# DRAM_DDR4.net
KiCad netlist of a schematic drawn in Altium Designer
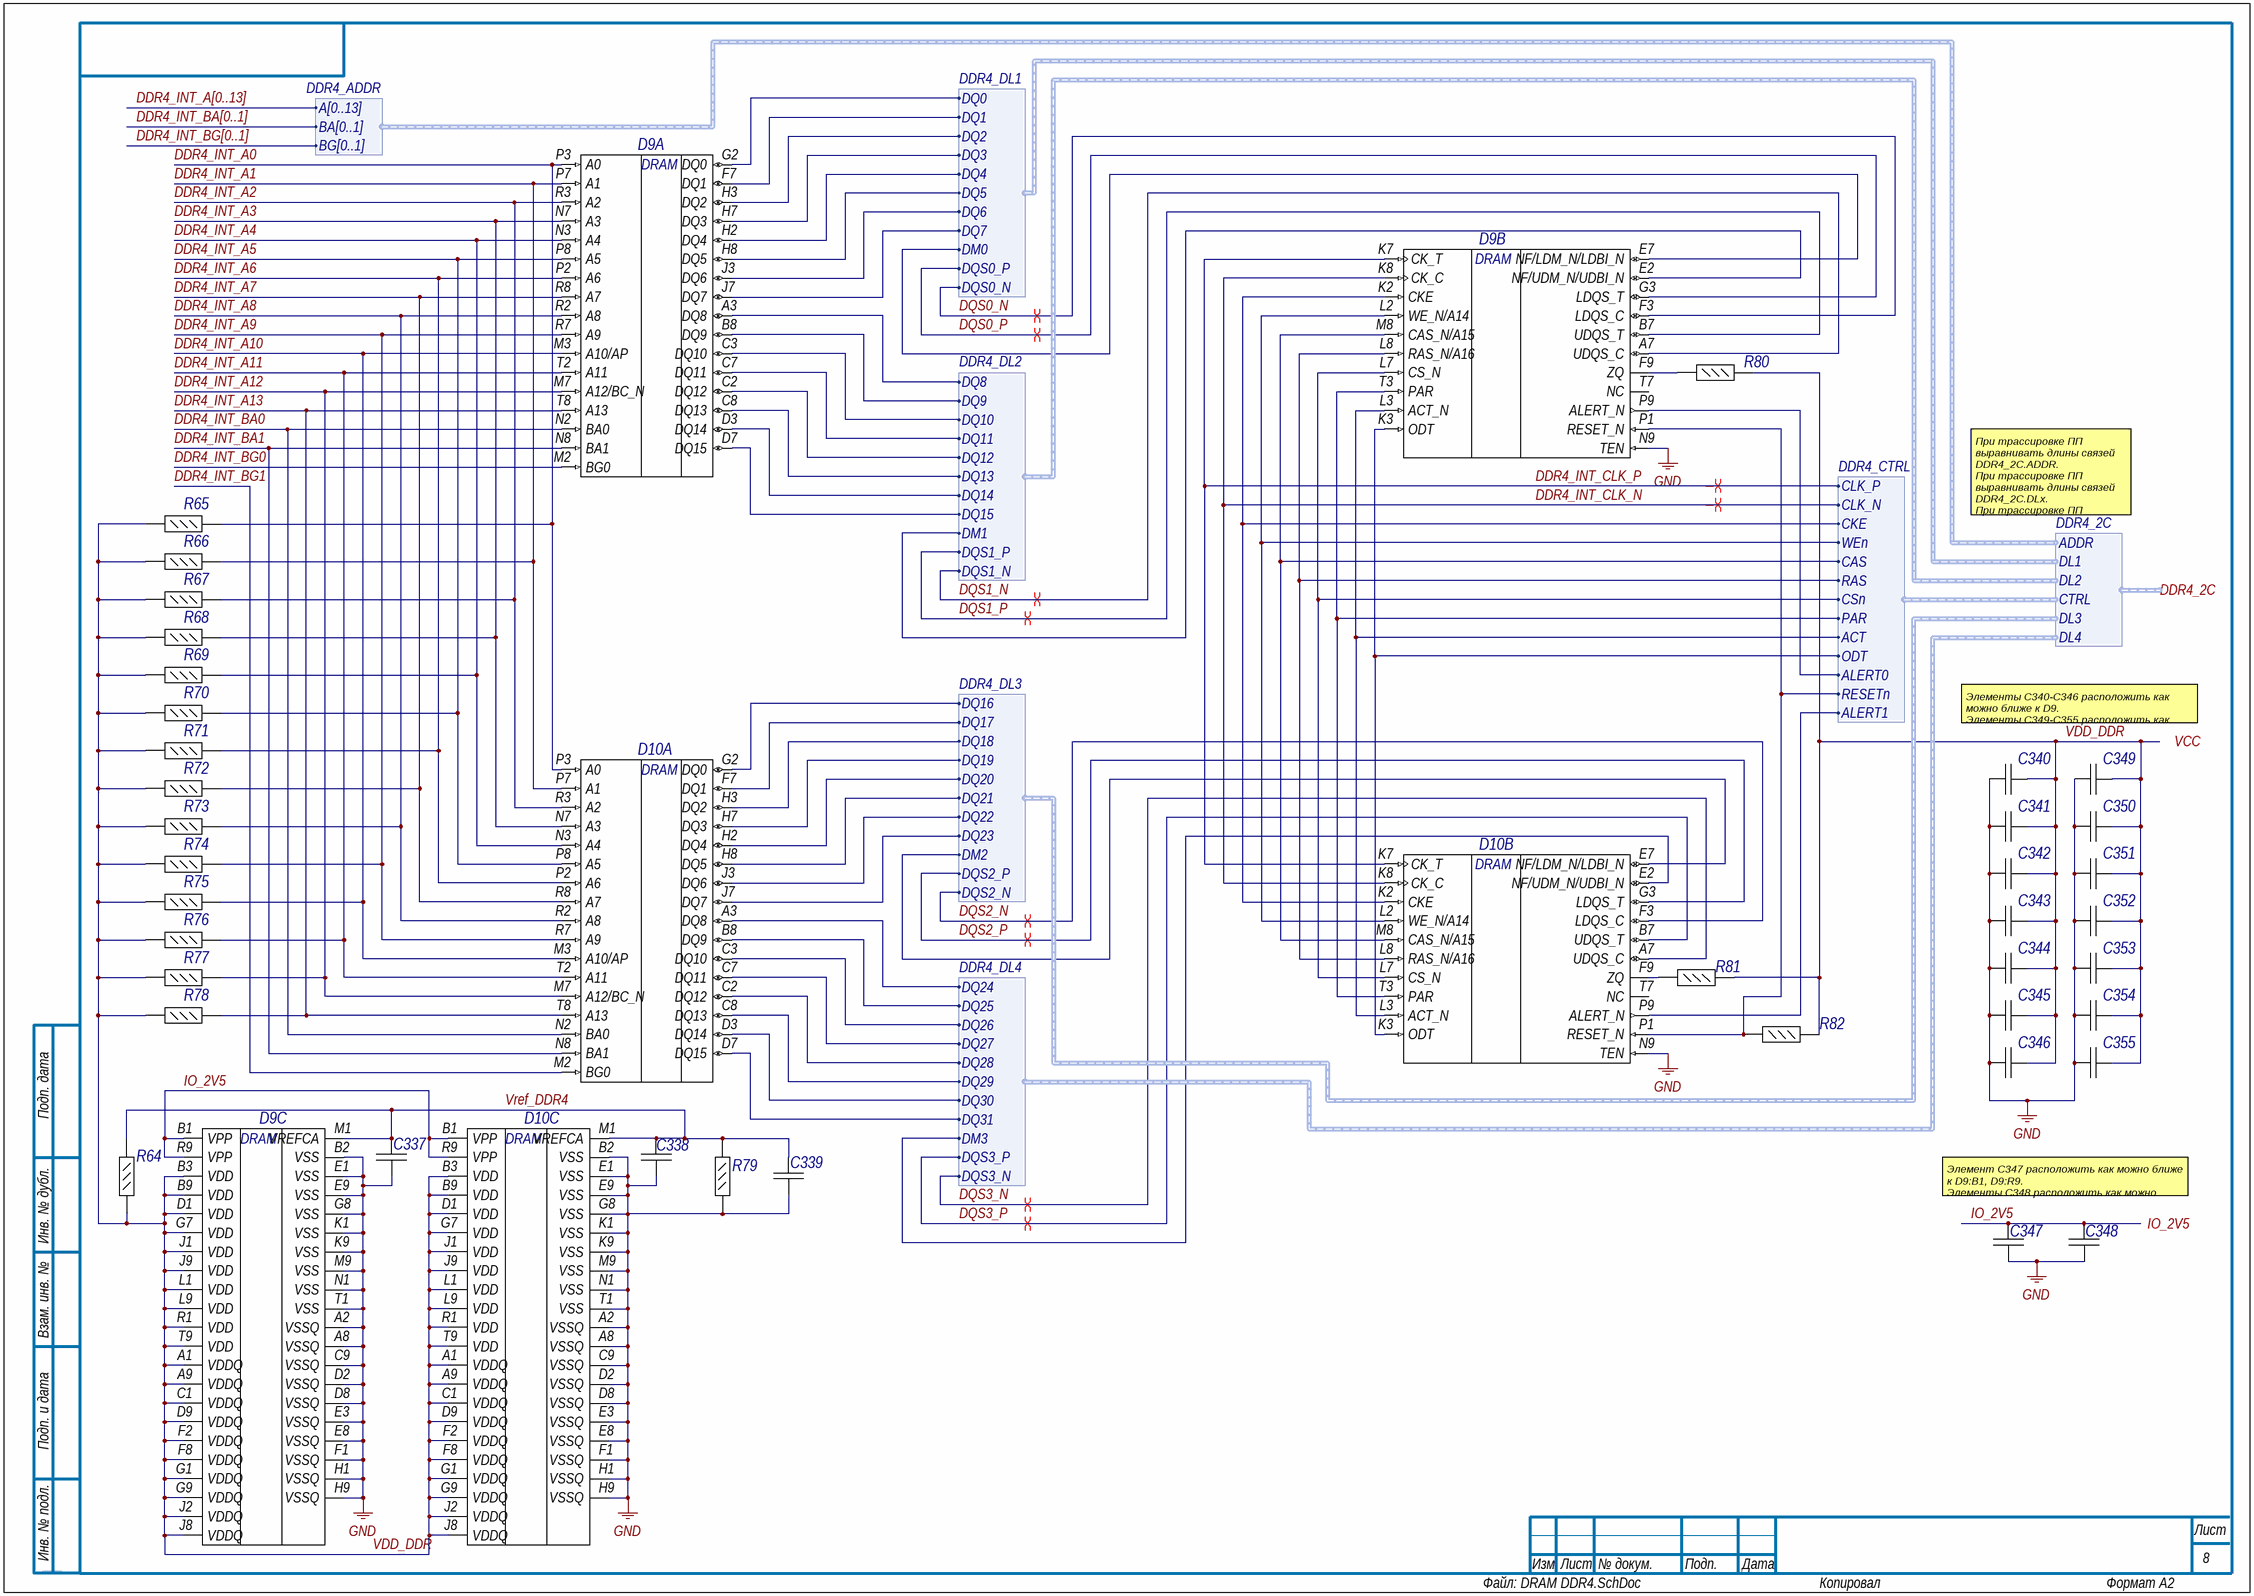
[diagram p0: DRAM DDR4.SchDoc]

(export (version "E")
  (design (tool "Eeschema 10.0.6"))
  (components
    (comp (ref "C337")
      (value "GRM033R60J104KE19D")
      (footprint "CAPC0603X33X15LL03T05")
      (description "Chip Capacitor, 100 nF, +/- 10%, 6.3 V, -55 to 85 degC, 0201 (0603 Metric), RoHS, Tape and Reel")
      (fields (field (name "TOLERANCE") "10%") (field (name "MANUFACTURER") "Basic Passives"))
      (libsource (lib "MiniPC DB") (part "CAP_NP"))
    )
    (comp (ref "C338")
      (value "GRM033R60J104KE19D")
      (footprint "CAPC0603X33X15LL03T05")
      (description "Chip Capacitor, 100 nF, +/- 10%, 6.3 V, -55 to 85 degC, 0201 (0603 Metric), RoHS, Tape and Reel")
      (fields (field (name "TOLERANCE") "10%") (field (name "MANUFACTURER") "Basic Passives"))
      (libsource (lib "MiniPC DB") (part "CAP_NP"))
    )
    (comp (ref "C339")
      (value "GRM033R60J104KE19D")
      (footprint "CAPC0603X33X15LL03T05")
      (description "Chip Capacitor, 100 nF, +/- 10%, 6.3 V, -55 to 85 degC, 0201 (0603 Metric), RoHS, Tape and Reel")
      (fields (field (name "TOLERANCE") "10%") (field (name "MANUFACTURER") "Basic Passives"))
      (libsource (lib "MiniPC DB") (part "CAP_NP"))
    )
    (comp (ref "C340")
      (value "GRM033R60J104KE19D")
      (footprint "CAPC0603X33X15LL03T05")
      (description "Chip Capacitor, 100 nF, +/- 10%, 6.3 V, -55 to 85 degC, 0201 (0603 Metric), RoHS, Tape and Reel")
      (fields (field (name "TOLERANCE") "10%") (field (name "MANUFACTURER") "Basic Passives"))
      (libsource (lib "MiniPC DB") (part "CAP_NP"))
    )
    (comp (ref "C341")
      (value "GRM033R60J104KE19D")
      (footprint "CAPC0603X33X15LL03T05")
      (description "Chip Capacitor, 100 nF, +/- 10%, 6.3 V, -55 to 85 degC, 0201 (0603 Metric), RoHS, Tape and Reel")
      (fields (field (name "TOLERANCE") "10%") (field (name "MANUFACTURER") "Basic Passives"))
      (libsource (lib "MiniPC DB") (part "CAP_NP"))
    )
    (comp (ref "C342")
      (value "GRM033R60J104KE19D")
      (footprint "CAPC0603X33X15LL03T05")
      (description "Chip Capacitor, 100 nF, +/- 10%, 6.3 V, -55 to 85 degC, 0201 (0603 Metric), RoHS, Tape and Reel")
      (fields (field (name "TOLERANCE") "10%") (field (name "MANUFACTURER") "Basic Passives"))
      (libsource (lib "MiniPC DB") (part "CAP_NP"))
    )
    (comp (ref "C343")
      (value "GRM033R60J104KE19D")
      (footprint "CAPC0603X33X15LL03T05")
      (description "Chip Capacitor, 100 nF, +/- 10%, 6.3 V, -55 to 85 degC, 0201 (0603 Metric), RoHS, Tape and Reel")
      (fields (field (name "TOLERANCE") "10%") (field (name "MANUFACTURER") "Basic Passives"))
      (libsource (lib "MiniPC DB") (part "CAP_NP"))
    )
    (comp (ref "C344")
      (value "GRM033R60J104KE19D")
      (footprint "CAPC0603X33X15LL03T05")
      (description "Chip Capacitor, 100 nF, +/- 10%, 6.3 V, -55 to 85 degC, 0201 (0603 Metric), RoHS, Tape and Reel")
      (fields (field (name "TOLERANCE") "10%") (field (name "MANUFACTURER") "Basic Passives"))
      (libsource (lib "MiniPC DB") (part "CAP_NP"))
    )
    (comp (ref "C345")
      (value "GRM033R60J104KE19D")
      (footprint "CAPC0603X33X15LL03T05")
      (description "Chip Capacitor, 100 nF, +/- 10%, 6.3 V, -55 to 85 degC, 0201 (0603 Metric), RoHS, Tape and Reel")
      (fields (field (name "TOLERANCE") "10%") (field (name "MANUFACTURER") "Basic Passives"))
      (libsource (lib "MiniPC DB") (part "CAP_NP"))
    )
    (comp (ref "C346")
      (value "GRM033R60J104KE19D")
      (footprint "CAPC0603X33X15LL03T05")
      (description "Chip Capacitor, 100 nF, +/- 10%, 6.3 V, -55 to 85 degC, 0201 (0603 Metric), RoHS, Tape and Reel")
      (fields (field (name "TOLERANCE") "10%") (field (name "MANUFACTURER") "Basic Passives"))
      (libsource (lib "MiniPC DB") (part "CAP_NP"))
    )
    (comp (ref "C347")
      (value "GRM033R60J104KE19D")
      (footprint "CAPC0603X33X15LL03T05")
      (description "Chip Capacitor, 100 nF, +/- 10%, 6.3 V, -55 to 85 degC, 0201 (0603 Metric), RoHS, Tape and Reel")
      (fields (field (name "TOLERANCE") "10%") (field (name "MANUFACTURER") "Basic Passives"))
      (libsource (lib "MiniPC DB") (part "CAP_NP"))
    )
    (comp (ref "C348")
      (value "GRM033R60J104KE19D")
      (footprint "CAPC0603X33X15LL03T05")
      (description "Chip Capacitor, 100 nF, +/- 10%, 6.3 V, -55 to 85 degC, 0201 (0603 Metric), RoHS, Tape and Reel")
      (fields (field (name "TOLERANCE") "10%") (field (name "MANUFACTURER") "Basic Passives"))
      (libsource (lib "MiniPC DB") (part "CAP_NP"))
    )
    (comp (ref "C349")
      (value "GRM033R60J104KE19D")
      (footprint "CAPC0603X33X15LL03T05")
      (description "Chip Capacitor, 100 nF, +/- 10%, 6.3 V, -55 to 85 degC, 0201 (0603 Metric), RoHS, Tape and Reel")
      (fields (field (name "TOLERANCE") "10%") (field (name "MANUFACTURER") "Basic Passives"))
      (libsource (lib "MiniPC DB") (part "CAP_NP"))
    )
    (comp (ref "C350")
      (value "GRM033R60J104KE19D")
      (footprint "CAPC0603X33X15LL03T05")
      (description "Chip Capacitor, 100 nF, +/- 10%, 6.3 V, -55 to 85 degC, 0201 (0603 Metric), RoHS, Tape and Reel")
      (fields (field (name "TOLERANCE") "10%") (field (name "MANUFACTURER") "Basic Passives"))
      (libsource (lib "MiniPC DB") (part "CAP_NP"))
    )
    (comp (ref "C351")
      (value "GRM033R60J104KE19D")
      (footprint "CAPC0603X33X15LL03T05")
      (description "Chip Capacitor, 100 nF, +/- 10%, 6.3 V, -55 to 85 degC, 0201 (0603 Metric), RoHS, Tape and Reel")
      (fields (field (name "TOLERANCE") "10%") (field (name "MANUFACTURER") "Basic Passives"))
      (libsource (lib "MiniPC DB") (part "CAP_NP"))
    )
    (comp (ref "C352")
      (value "GRM033R60J104KE19D")
      (footprint "CAPC0603X33X15LL03T05")
      (description "Chip Capacitor, 100 nF, +/- 10%, 6.3 V, -55 to 85 degC, 0201 (0603 Metric), RoHS, Tape and Reel")
      (fields (field (name "TOLERANCE") "10%") (field (name "MANUFACTURER") "Basic Passives"))
      (libsource (lib "MiniPC DB") (part "CAP_NP"))
    )
    (comp (ref "C353")
      (value "GRM033R60J104KE19D")
      (footprint "CAPC0603X33X15LL03T05")
      (description "Chip Capacitor, 100 nF, +/- 10%, 6.3 V, -55 to 85 degC, 0201 (0603 Metric), RoHS, Tape and Reel")
      (fields (field (name "TOLERANCE") "10%") (field (name "MANUFACTURER") "Basic Passives"))
      (libsource (lib "MiniPC DB") (part "CAP_NP"))
    )
    (comp (ref "C354")
      (value "GRM033R60J104KE19D")
      (footprint "CAPC0603X33X15LL03T05")
      (description "Chip Capacitor, 100 nF, +/- 10%, 6.3 V, -55 to 85 degC, 0201 (0603 Metric), RoHS, Tape and Reel")
      (fields (field (name "TOLERANCE") "10%") (field (name "MANUFACTURER") "Basic Passives"))
      (libsource (lib "MiniPC DB") (part "CAP_NP"))
    )
    (comp (ref "C355")
      (value "GRM033R60J104KE19D")
      (footprint "CAPC0603X33X15LL03T05")
      (description "Chip Capacitor, 100 nF, +/- 10%, 6.3 V, -55 to 85 degC, 0201 (0603 Metric), RoHS, Tape and Reel")
      (fields (field (name "TOLERANCE") "10%") (field (name "MANUFACTURER") "Basic Passives"))
      (libsource (lib "MiniPC DB") (part "CAP_NP"))
    )
    (comp (ref "D9")
      (value "MT40A512M16LY-107E")
      (footprint "MICT-LY-96_A")
      (description "8 Gb DDR4 SDRAM, 512 Meg x 16, 1.2 V, 0 to 95 degC, 96-Ball FBGA (LY), RoHS")
      (libsource (lib "MiniPC DB") (part "MT40A512M16"))
    )
    (comp (ref "D10")
      (value "MT40A512M16LY-107E")
      (footprint "MICT-LY-96_A")
      (description "8 Gb DDR4 SDRAM, 512 Meg x 16, 1.2 V, 0 to 95 degC, 96-Ball FBGA (LY), RoHS")
      (libsource (lib "MiniPC DB") (part "MT40A512M16"))
    )
    (comp (ref "R64")
      (value "ERJ-2RKF2400X")
      (footprint "RESC1005X40X25LL05T05")
      (description "Chip Resistor, 240 Ohm, +/- 1%, 100 mW, -55 to 155 degC, 0402 (1005 Metric), RoHS, Tape and Reel")
      (fields (field (name "TOLERANCE") "1%"))
      (libsource (lib "") (part "RES-0.05_1"))
    )
    (comp (ref "R65")
      (value "RC0402JR-0739RL")
      (footprint "RESC1005X40X25LL05T05")
      (description "Chip Resistor, 39 Ohm, +/- 5%, 0.063 W, -55 to 155 degC, 0402 (1005 Metric), RoHS, Tape and Reel")
      (fields (field (name "TOLERANCE") "5%"))
      (libsource (lib "MiniPC DB") (part "RES-0.05"))
    )
    (comp (ref "R66")
      (value "RC0402JR-0739RL")
      (footprint "RESC1005X40X25LL05T05")
      (description "Chip Resistor, 39 Ohm, +/- 5%, 0.063 W, -55 to 155 degC, 0402 (1005 Metric), RoHS, Tape and Reel")
      (fields (field (name "TOLERANCE") "5%"))
      (libsource (lib "MiniPC DB") (part "RES-0.05"))
    )
    (comp (ref "R67")
      (value "RC0402JR-0739RL")
      (footprint "RESC1005X40X25LL05T05")
      (description "Chip Resistor, 39 Ohm, +/- 5%, 0.063 W, -55 to 155 degC, 0402 (1005 Metric), RoHS, Tape and Reel")
      (fields (field (name "TOLERANCE") "5%"))
      (libsource (lib "MiniPC DB") (part "RES-0.05"))
    )
    (comp (ref "R68")
      (value "RC0402JR-0739RL")
      (footprint "RESC1005X40X25LL05T05")
      (description "Chip Resistor, 39 Ohm, +/- 5%, 0.063 W, -55 to 155 degC, 0402 (1005 Metric), RoHS, Tape and Reel")
      (fields (field (name "TOLERANCE") "5%"))
      (libsource (lib "MiniPC DB") (part "RES-0.05"))
    )
    (comp (ref "R69")
      (value "RC0402JR-0739RL")
      (footprint "RESC1005X40X25LL05T05")
      (description "Chip Resistor, 39 Ohm, +/- 5%, 0.063 W, -55 to 155 degC, 0402 (1005 Metric), RoHS, Tape and Reel")
      (fields (field (name "TOLERANCE") "5%"))
      (libsource (lib "MiniPC DB") (part "RES-0.05"))
    )
    (comp (ref "R70")
      (value "RC0402JR-0739RL")
      (footprint "RESC1005X40X25LL05T05")
      (description "Chip Resistor, 39 Ohm, +/- 5%, 0.063 W, -55 to 155 degC, 0402 (1005 Metric), RoHS, Tape and Reel")
      (fields (field (name "TOLERANCE") "5%"))
      (libsource (lib "MiniPC DB") (part "RES-0.05"))
    )
    (comp (ref "R71")
      (value "RC0402JR-0739RL")
      (footprint "RESC1005X40X25LL05T05")
      (description "Chip Resistor, 39 Ohm, +/- 5%, 0.063 W, -55 to 155 degC, 0402 (1005 Metric), RoHS, Tape and Reel")
      (fields (field (name "TOLERANCE") "5%"))
      (libsource (lib "MiniPC DB") (part "RES-0.05"))
    )
    (comp (ref "R72")
      (value "RC0402JR-0739RL")
      (footprint "RESC1005X40X25LL05T05")
      (description "Chip Resistor, 39 Ohm, +/- 5%, 0.063 W, -55 to 155 degC, 0402 (1005 Metric), RoHS, Tape and Reel")
      (fields (field (name "TOLERANCE") "5%"))
      (libsource (lib "MiniPC DB") (part "RES-0.05"))
    )
    (comp (ref "R73")
      (value "RC0402JR-0739RL")
      (footprint "RESC1005X40X25LL05T05")
      (description "Chip Resistor, 39 Ohm, +/- 5%, 0.063 W, -55 to 155 degC, 0402 (1005 Metric), RoHS, Tape and Reel")
      (fields (field (name "TOLERANCE") "5%"))
      (libsource (lib "MiniPC DB") (part "RES-0.05"))
    )
    (comp (ref "R74")
      (value "RC0402JR-0739RL")
      (footprint "RESC1005X40X25LL05T05")
      (description "Chip Resistor, 39 Ohm, +/- 5%, 0.063 W, -55 to 155 degC, 0402 (1005 Metric), RoHS, Tape and Reel")
      (fields (field (name "TOLERANCE") "5%"))
      (libsource (lib "MiniPC DB") (part "RES-0.05"))
    )
    (comp (ref "R75")
      (value "RC0402JR-0739RL")
      (footprint "RESC1005X40X25LL05T05")
      (description "Chip Resistor, 39 Ohm, +/- 5%, 0.063 W, -55 to 155 degC, 0402 (1005 Metric), RoHS, Tape and Reel")
      (fields (field (name "TOLERANCE") "5%"))
      (libsource (lib "MiniPC DB") (part "RES-0.05"))
    )
    (comp (ref "R76")
      (value "RC0402JR-0739RL")
      (footprint "RESC1005X40X25LL05T05")
      (description "Chip Resistor, 39 Ohm, +/- 5%, 0.063 W, -55 to 155 degC, 0402 (1005 Metric), RoHS, Tape and Reel")
      (fields (field (name "TOLERANCE") "5%"))
      (libsource (lib "MiniPC DB") (part "RES-0.05"))
    )
    (comp (ref "R77")
      (value "RC0402JR-0739RL")
      (footprint "RESC1005X40X25LL05T05")
      (description "Chip Resistor, 39 Ohm, +/- 5%, 0.063 W, -55 to 155 degC, 0402 (1005 Metric), RoHS, Tape and Reel")
      (fields (field (name "TOLERANCE") "5%"))
      (libsource (lib "MiniPC DB") (part "RES-0.05"))
    )
    (comp (ref "R78")
      (value "RC0402JR-0739RL")
      (footprint "RESC1005X40X25LL05T05")
      (description "Chip Resistor, 39 Ohm, +/- 5%, 0.063 W, -55 to 155 degC, 0402 (1005 Metric), RoHS, Tape and Reel")
      (fields (field (name "TOLERANCE") "5%"))
      (libsource (lib "MiniPC DB") (part "RES-0.05"))
    )
    (comp (ref "R79")
      (value "ERJ-2RKF2400X")
      (footprint "RESC1005X40X25LL05T05")
      (description "Chip Resistor, 240 Ohm, +/- 1%, 100 mW, -55 to 155 degC, 0402 (1005 Metric), RoHS, Tape and Reel")
      (fields (field (name "TOLERANCE") "1%"))
      (libsource (lib "") (part "RES-0.05_1"))
    )
    (comp (ref "R80")
      (value "ERJ-2RKF2400X")
      (footprint "RESC1005X40X25LL05T05")
      (description "Chip Resistor, 240 Ohm, +/- 1%, 100 mW, -55 to 155 degC, 0402 (1005 Metric), RoHS, Tape and Reel")
      (fields (field (name "TOLERANCE") "1%"))
      (libsource (lib "MiniPC DB") (part "RES-0.05"))
    )
    (comp (ref "R81")
      (value "ERJ-2RKF2400X")
      (footprint "RESC1005X40X25LL05T05")
      (description "Chip Resistor, 240 Ohm, +/- 1%, 100 mW, -55 to 155 degC, 0402 (1005 Metric), RoHS, Tape and Reel")
      (fields (field (name "TOLERANCE") "1%"))
      (libsource (lib "MiniPC DB") (part "RES-0.05"))
    )
    (comp (ref "R82")
      (value "ERJ-2RKF2001X")
      (footprint "RESC1005X40X25LL05T05")
      (description "Chip Resistor, 2 KOhm, +/- 1%, 100 mW, -55 to 155 degC, 0402 (1005 Metric), RoHS, Tape and Reel")
      (fields (field (name "TOLERANCE") "1%") (field (name "MANUFACTURER") "Basic Passives"))
      (libsource (lib "MiniPC DB") (part "RES-0.05"))
    )
  )
  (nets
    (net (code "8") (name "/ACT") (class "Default")
      (node (ref "D10") (pin "L3") (pinfunction "ACT_N_L3") (pintype "input"))
      (node (ref "D9") (pin "L3") (pinfunction "ACT_N_L3") (pintype "input"))
    )
    (net (code "9") (name "/ALERT0") (class "Default")
      (node (ref "D9") (pin "P9") (pinfunction "ALERT_N_P9") (pintype "output"))
    )
    (net (code "10") (name "/ALERT1") (class "Default")
      (node (ref "D10") (pin "P9") (pinfunction "ALERT_N_P9") (pintype "output"))
    )
    (net (code "11") (name "/CAS") (class "Default")
      (node (ref "D10") (pin "M8") (pinfunction "CAS_N/A15_M8") (pintype "input"))
      (node (ref "D9") (pin "M8") (pinfunction "CAS_N/A15_M8") (pintype "input"))
    )
    (net (code "12") (name "/CKE") (class "Default")
      (node (ref "D10") (pin "K2") (pinfunction "CKE_K2") (pintype "input"))
      (node (ref "D9") (pin "K2") (pinfunction "CKE_K2") (pintype "input"))
    )
    (net (code "13") (name "/CSn") (class "Default")
      (node (ref "D10") (pin "L7") (pinfunction "CS_N_L7") (pintype "input"))
      (node (ref "D9") (pin "L7") (pinfunction "CS_N_L7") (pintype "input"))
    )
    (net (code "15") (name "/DDR4_INT_A0") (class "Default")
      (node (ref "D10") (pin "P3") (pinfunction "A0_P3") (pintype "input"))
      (node (ref "D9") (pin "P3") (pinfunction "A0_P3") (pintype "input"))
      (node (ref "R65") (pin "2") (pinfunction "2_2") (pintype "passive"))
    )
    (net (code "16") (name "/DDR4_INT_A1") (class "Default")
      (node (ref "D10") (pin "P7") (pinfunction "A1_P7") (pintype "input"))
      (node (ref "D9") (pin "P7") (pinfunction "A1_P7") (pintype "input"))
      (node (ref "R66") (pin "2") (pinfunction "2_2") (pintype "passive"))
    )
    (net (code "17") (name "/DDR4_INT_A2") (class "Default")
      (node (ref "D10") (pin "R3") (pinfunction "A2_R3") (pintype "input"))
      (node (ref "D9") (pin "R3") (pinfunction "A2_R3") (pintype "input"))
      (node (ref "R67") (pin "2") (pinfunction "2_2") (pintype "passive"))
    )
    (net (code "18") (name "/DDR4_INT_A3") (class "Default")
      (node (ref "D10") (pin "N7") (pinfunction "A3_N7") (pintype "input"))
      (node (ref "D9") (pin "N7") (pinfunction "A3_N7") (pintype "input"))
      (node (ref "R68") (pin "2") (pinfunction "2_2") (pintype "passive"))
    )
    (net (code "19") (name "/DDR4_INT_A4") (class "Default")
      (node (ref "D10") (pin "N3") (pinfunction "A4_N3") (pintype "input"))
      (node (ref "D9") (pin "N3") (pinfunction "A4_N3") (pintype "input"))
      (node (ref "R69") (pin "2") (pinfunction "2_2") (pintype "passive"))
    )
    (net (code "20") (name "/DDR4_INT_A5") (class "Default")
      (node (ref "D10") (pin "P8") (pinfunction "A5_P8") (pintype "input"))
      (node (ref "D9") (pin "P8") (pinfunction "A5_P8") (pintype "input"))
      (node (ref "R70") (pin "2") (pinfunction "2_2") (pintype "passive"))
    )
    (net (code "21") (name "/DDR4_INT_A6") (class "Default")
      (node (ref "D10") (pin "P2") (pinfunction "A6_P2") (pintype "input"))
      (node (ref "D9") (pin "P2") (pinfunction "A6_P2") (pintype "input"))
      (node (ref "R71") (pin "2") (pinfunction "2_2") (pintype "passive"))
    )
    (net (code "22") (name "/DDR4_INT_A7") (class "Default")
      (node (ref "D10") (pin "R8") (pinfunction "A7_R8") (pintype "input"))
      (node (ref "D9") (pin "R8") (pinfunction "A7_R8") (pintype "input"))
      (node (ref "R72") (pin "2") (pinfunction "2_2") (pintype "passive"))
    )
    (net (code "23") (name "/DDR4_INT_A8") (class "Default")
      (node (ref "D10") (pin "R2") (pinfunction "A8_R2") (pintype "input"))
      (node (ref "D9") (pin "R2") (pinfunction "A8_R2") (pintype "input"))
      (node (ref "R73") (pin "2") (pinfunction "2_2") (pintype "passive"))
    )
    (net (code "24") (name "/DDR4_INT_A9") (class "Default")
      (node (ref "D10") (pin "R7") (pinfunction "A9_R7") (pintype "input"))
      (node (ref "D9") (pin "R7") (pinfunction "A9_R7") (pintype "input"))
      (node (ref "R74") (pin "2") (pinfunction "2_2") (pintype "passive"))
    )
    (net (code "25") (name "/DDR4_INT_A10") (class "Default")
      (node (ref "D10") (pin "M3") (pinfunction "A10/AP_M3") (pintype "input"))
      (node (ref "D9") (pin "M3") (pinfunction "A10/AP_M3") (pintype "input"))
      (node (ref "R75") (pin "2") (pinfunction "2_2") (pintype "passive"))
    )
    (net (code "26") (name "/DDR4_INT_A11") (class "Default")
      (node (ref "D10") (pin "T2") (pinfunction "A11_T2") (pintype "input"))
      (node (ref "D9") (pin "T2") (pinfunction "A11_T2") (pintype "input"))
      (node (ref "R76") (pin "2") (pinfunction "2_2") (pintype "passive"))
    )
    (net (code "27") (name "/DDR4_INT_A12") (class "Default")
      (node (ref "D10") (pin "M7") (pinfunction "A12/BC_N_M7") (pintype "input"))
      (node (ref "D9") (pin "M7") (pinfunction "A12/BC_N_M7") (pintype "input"))
      (node (ref "R77") (pin "2") (pinfunction "2_2") (pintype "passive"))
    )
    (net (code "28") (name "/DDR4_INT_A13") (class "Default")
      (node (ref "D10") (pin "T8") (pinfunction "A13_T8") (pintype "input"))
      (node (ref "D9") (pin "T8") (pinfunction "A13_T8") (pintype "input"))
      (node (ref "R78") (pin "2") (pinfunction "2_2") (pintype "passive"))
    )
    (net (code "30") (name "/DDR4_INT_BA0") (class "Default")
      (node (ref "D10") (pin "N2") (pinfunction "BA0_N2") (pintype "input"))
      (node (ref "D9") (pin "N2") (pinfunction "BA0_N2") (pintype "input"))
    )
    (net (code "31") (name "/DDR4_INT_BA1") (class "Default")
      (node (ref "D10") (pin "N8") (pinfunction "BA1_N8") (pintype "input"))
      (node (ref "D9") (pin "N8") (pinfunction "BA1_N8") (pintype "input"))
    )
    (net (code "33") (name "/DDR4_INT_BG0") (class "Default")
      (node (ref "D9") (pin "M2") (pinfunction "BG0_M2") (pintype "input"))
    )
    (net (code "34") (name "/DDR4_INT_BG1") (class "Default")
      (node (ref "D10") (pin "M2") (pinfunction "BG0_M2") (pintype "input"))
    )
    (net (code "36") (name "/DDR4_INT_CLK_N") (class "Default")
      (node (ref "D10") (pin "K8") (pinfunction "CK_C_K8") (pintype "input"))
      (node (ref "D9") (pin "K8") (pinfunction "CK_C_K8") (pintype "input"))
    )
    (net (code "37") (name "/DDR4_INT_CLK_P") (class "Default")
      (node (ref "D10") (pin "K7") (pinfunction "CK_T_K7") (pintype "input"))
      (node (ref "D9") (pin "K7") (pinfunction "CK_T_K7") (pintype "input"))
    )
    (net (code "38") (name "/DM0") (class "Default")
      (node (ref "D9") (pin "E7") (pinfunction "NF/LDM_N/LDBI_N_E7") (pintype "bidirectional"))
    )
    (net (code "39") (name "/DM1") (class "Default")
      (node (ref "D9") (pin "E2") (pinfunction "NF/UDM_N/UDBI_N_E2") (pintype "bidirectional"))
    )
    (net (code "40") (name "/DM2") (class "Default")
      (node (ref "D10") (pin "E7") (pinfunction "NF/LDM_N/LDBI_N_E7") (pintype "bidirectional"))
    )
    (net (code "41") (name "/DM3") (class "Default")
      (node (ref "D10") (pin "E2") (pinfunction "NF/UDM_N/UDBI_N_E2") (pintype "bidirectional"))
    )
    (net (code "42") (name "/DQ0") (class "Default")
      (node (ref "D9") (pin "G2") (pinfunction "DQ0_G2") (pintype "bidirectional"))
    )
    (net (code "43") (name "/DQ1") (class "Default")
      (node (ref "D9") (pin "F7") (pinfunction "DQ1_F7") (pintype "bidirectional"))
    )
    (net (code "44") (name "/DQ2") (class "Default")
      (node (ref "D9") (pin "H3") (pinfunction "DQ2_H3") (pintype "bidirectional"))
    )
    (net (code "45") (name "/DQ3") (class "Default")
      (node (ref "D9") (pin "H7") (pinfunction "DQ3_H7") (pintype "bidirectional"))
    )
    (net (code "46") (name "/DQ4") (class "Default")
      (node (ref "D9") (pin "H2") (pinfunction "DQ4_H2") (pintype "bidirectional"))
    )
    (net (code "47") (name "/DQ5") (class "Default")
      (node (ref "D9") (pin "H8") (pinfunction "DQ5_H8") (pintype "bidirectional"))
    )
    (net (code "48") (name "/DQ6") (class "Default")
      (node (ref "D9") (pin "J3") (pinfunction "DQ6_J3") (pintype "bidirectional"))
    )
    (net (code "49") (name "/DQ7") (class "Default")
      (node (ref "D9") (pin "J7") (pinfunction "DQ7_J7") (pintype "bidirectional"))
    )
    (net (code "50") (name "/DQ8") (class "Default")
      (node (ref "D9") (pin "A3") (pinfunction "DQ8_A3") (pintype "bidirectional"))
    )
    (net (code "51") (name "/DQ9") (class "Default")
      (node (ref "D9") (pin "B8") (pinfunction "DQ9_B8") (pintype "bidirectional"))
    )
    (net (code "52") (name "/DQ10") (class "Default")
      (node (ref "D9") (pin "C3") (pinfunction "DQ10_C3") (pintype "bidirectional"))
    )
    (net (code "53") (name "/DQ11") (class "Default")
      (node (ref "D9") (pin "C7") (pinfunction "DQ11_C7") (pintype "bidirectional"))
    )
    (net (code "54") (name "/DQ12") (class "Default")
      (node (ref "D9") (pin "C2") (pinfunction "DQ12_C2") (pintype "bidirectional"))
    )
    (net (code "55") (name "/DQ13") (class "Default")
      (node (ref "D9") (pin "C8") (pinfunction "DQ13_C8") (pintype "bidirectional"))
    )
    (net (code "56") (name "/DQ14") (class "Default")
      (node (ref "D9") (pin "D3") (pinfunction "DQ14_D3") (pintype "bidirectional"))
    )
    (net (code "57") (name "/DQ15") (class "Default")
      (node (ref "D9") (pin "D7") (pinfunction "DQ15_D7") (pintype "bidirectional"))
    )
    (net (code "58") (name "/DQ16") (class "Default")
      (node (ref "D10") (pin "G2") (pinfunction "DQ0_G2") (pintype "bidirectional"))
    )
    (net (code "59") (name "/DQ17") (class "Default")
      (node (ref "D10") (pin "F7") (pinfunction "DQ1_F7") (pintype "bidirectional"))
    )
    (net (code "60") (name "/DQ18") (class "Default")
      (node (ref "D10") (pin "H3") (pinfunction "DQ2_H3") (pintype "bidirectional"))
    )
    (net (code "61") (name "/DQ19") (class "Default")
      (node (ref "D10") (pin "H7") (pinfunction "DQ3_H7") (pintype "bidirectional"))
    )
    (net (code "62") (name "/DQ20") (class "Default")
      (node (ref "D10") (pin "H2") (pinfunction "DQ4_H2") (pintype "bidirectional"))
    )
    (net (code "63") (name "/DQ21") (class "Default")
      (node (ref "D10") (pin "H8") (pinfunction "DQ5_H8") (pintype "bidirectional"))
    )
    (net (code "64") (name "/DQ22") (class "Default")
      (node (ref "D10") (pin "J3") (pinfunction "DQ6_J3") (pintype "bidirectional"))
    )
    (net (code "65") (name "/DQ23") (class "Default")
      (node (ref "D10") (pin "J7") (pinfunction "DQ7_J7") (pintype "bidirectional"))
    )
    (net (code "66") (name "/DQ24") (class "Default")
      (node (ref "D10") (pin "A3") (pinfunction "DQ8_A3") (pintype "bidirectional"))
    )
    (net (code "67") (name "/DQ25") (class "Default")
      (node (ref "D10") (pin "B8") (pinfunction "DQ9_B8") (pintype "bidirectional"))
    )
    (net (code "68") (name "/DQ26") (class "Default")
      (node (ref "D10") (pin "C3") (pinfunction "DQ10_C3") (pintype "bidirectional"))
    )
    (net (code "69") (name "/DQ27") (class "Default")
      (node (ref "D10") (pin "C7") (pinfunction "DQ11_C7") (pintype "bidirectional"))
    )
    (net (code "70") (name "/DQ28") (class "Default")
      (node (ref "D10") (pin "C2") (pinfunction "DQ12_C2") (pintype "bidirectional"))
    )
    (net (code "71") (name "/DQ29") (class "Default")
      (node (ref "D10") (pin "C8") (pinfunction "DQ13_C8") (pintype "bidirectional"))
    )
    (net (code "72") (name "/DQ30") (class "Default")
      (node (ref "D10") (pin "D3") (pinfunction "DQ14_D3") (pintype "bidirectional"))
    )
    (net (code "73") (name "/DQ31") (class "Default")
      (node (ref "D10") (pin "D7") (pinfunction "DQ15_D7") (pintype "bidirectional"))
    )
    (net (code "74") (name "/DQS0_N") (class "Default")
      (node (ref "D9") (pin "F3") (pinfunction "LDQS_C_F3") (pintype "bidirectional"))
    )
    (net (code "75") (name "/DQS0_P") (class "Default")
      (node (ref "D9") (pin "G3") (pinfunction "LDQS_T_G3") (pintype "bidirectional"))
    )
    (net (code "76") (name "/DQS1_N") (class "Default")
      (node (ref "D9") (pin "A7") (pinfunction "UDQS_C_A7") (pintype "bidirectional"))
    )
    (net (code "77") (name "/DQS1_P") (class "Default")
      (node (ref "D9") (pin "B7") (pinfunction "UDQS_T_B7") (pintype "bidirectional"))
    )
    (net (code "78") (name "/DQS2_N") (class "Default")
      (node (ref "D10") (pin "F3") (pinfunction "LDQS_C_F3") (pintype "bidirectional"))
    )
    (net (code "79") (name "/DQS2_P") (class "Default")
      (node (ref "D10") (pin "G3") (pinfunction "LDQS_T_G3") (pintype "bidirectional"))
    )
    (net (code "80") (name "/DQS3_N") (class "Default")
      (node (ref "D10") (pin "A7") (pinfunction "UDQS_C_A7") (pintype "bidirectional"))
    )
    (net (code "81") (name "/DQS3_P") (class "Default")
      (node (ref "D10") (pin "B7") (pinfunction "UDQS_T_B7") (pintype "bidirectional"))
    )
    (net (code "82") (name "/IO_2V5") (class "Default")
      (node (ref "C347") (pin "2") (pinfunction "2_2") (pintype "passive"))
      (node (ref "C348") (pin "2") (pinfunction "2_2") (pintype "passive"))
      (node (ref "D10") (pin "B1") (pinfunction "VPP_B1") (pintype "power_in"))
      (node (ref "D10") (pin "R9") (pinfunction "VPP_R9") (pintype "power_in"))
      (node (ref "D9") (pin "B1") (pinfunction "VPP_B1") (pintype "power_in"))
      (node (ref "D9") (pin "R9") (pinfunction "VPP_R9") (pintype "power_in"))
    )
    (net (code "83") (name "/ODT") (class "Default")
      (node (ref "D10") (pin "K3") (pinfunction "ODT_K3") (pintype "input"))
      (node (ref "D9") (pin "K3") (pinfunction "ODT_K3") (pintype "input"))
    )
    (net (code "84") (name "/PAR") (class "Default")
      (node (ref "D10") (pin "T3") (pinfunction "PAR_T3") (pintype "input"))
      (node (ref "D9") (pin "T3") (pinfunction "PAR_T3") (pintype "input"))
    )
    (net (code "85") (name "/RAS") (class "Default")
      (node (ref "D10") (pin "L8") (pinfunction "RAS_N/A16_L8") (pintype "input"))
      (node (ref "D9") (pin "L8") (pinfunction "RAS_N/A16_L8") (pintype "input"))
    )
    (net (code "86") (name "/RESETn") (class "Default")
      (node (ref "D10") (pin "P1") (pinfunction "RESET_N_P1") (pintype "input"))
      (node (ref "D9") (pin "P1") (pinfunction "RESET_N_P1") (pintype "input"))
      (node (ref "R82") (pin "1") (pinfunction "1_1") (pintype "passive"))
    )
    (net (code "87") (name "/VDD_DDR") (class "Default")
      (node (ref "C340") (pin "2") (pinfunction "2_2") (pintype "passive"))
      (node (ref "C341") (pin "2") (pinfunction "2_2") (pintype "passive"))
      (node (ref "C342") (pin "2") (pinfunction "2_2") (pintype "passive"))
      (node (ref "C343") (pin "2") (pinfunction "2_2") (pintype "passive"))
      (node (ref "C344") (pin "2") (pinfunction "2_2") (pintype "passive"))
      (node (ref "C345") (pin "2") (pinfunction "2_2") (pintype "passive"))
      (node (ref "C346") (pin "2") (pinfunction "2_2") (pintype "passive"))
      (node (ref "C349") (pin "2") (pinfunction "2_2") (pintype "passive"))
      (node (ref "C350") (pin "2") (pinfunction "2_2") (pintype "passive"))
      (node (ref "C351") (pin "2") (pinfunction "2_2") (pintype "passive"))
      (node (ref "C352") (pin "2") (pinfunction "2_2") (pintype "passive"))
      (node (ref "C353") (pin "2") (pinfunction "2_2") (pintype "passive"))
      (node (ref "C354") (pin "2") (pinfunction "2_2") (pintype "passive"))
      (node (ref "C355") (pin "2") (pinfunction "2_2") (pintype "passive"))
      (node (ref "D10") (pin "A1") (pinfunction "VDDQ_A1") (pintype "power_in"))
      (node (ref "D10") (pin "A9") (pinfunction "VDDQ_A9") (pintype "power_in"))
      (node (ref "D10") (pin "B3") (pinfunction "VDD_B3") (pintype "passive"))
      (node (ref "D10") (pin "B9") (pinfunction "VDD_B9") (pintype "passive"))
      (node (ref "D10") (pin "C1") (pinfunction "VDDQ_C1") (pintype "power_in"))
      (node (ref "D10") (pin "D1") (pinfunction "VDD_D1") (pintype "passive"))
      (node (ref "D10") (pin "D9") (pinfunction "VDDQ_D9") (pintype "power_in"))
      (node (ref "D10") (pin "F2") (pinfunction "VDDQ_F2") (pintype "power_in"))
      (node (ref "D10") (pin "F8") (pinfunction "VDDQ_F8") (pintype "power_in"))
      (node (ref "D10") (pin "G1") (pinfunction "VDDQ_G1") (pintype "power_in"))
      (node (ref "D10") (pin "G7") (pinfunction "VDD_G7") (pintype "passive"))
      (node (ref "D10") (pin "G9") (pinfunction "VDDQ_G9") (pintype "power_in"))
      (node (ref "D10") (pin "J1") (pinfunction "VDD_J1") (pintype "passive"))
      (node (ref "D10") (pin "J2") (pinfunction "VDDQ_J2") (pintype "power_in"))
      (node (ref "D10") (pin "J8") (pinfunction "VDDQ_J8") (pintype "power_in"))
      (node (ref "D10") (pin "J9") (pinfunction "VDD_J9") (pintype "passive"))
      (node (ref "D10") (pin "L1") (pinfunction "VDD_L1") (pintype "passive"))
      (node (ref "D10") (pin "L9") (pinfunction "VDD_L9") (pintype "passive"))
      (node (ref "D10") (pin "R1") (pinfunction "VDD_R1") (pintype "passive"))
      (node (ref "D10") (pin "T9") (pinfunction "VDD_T9") (pintype "passive"))
      (node (ref "D9") (pin "A1") (pinfunction "VDDQ_A1") (pintype "power_in"))
      (node (ref "D9") (pin "A9") (pinfunction "VDDQ_A9") (pintype "power_in"))
      (node (ref "D9") (pin "B3") (pinfunction "VDD_B3") (pintype "passive"))
      (node (ref "D9") (pin "B9") (pinfunction "VDD_B9") (pintype "passive"))
      (node (ref "D9") (pin "C1") (pinfunction "VDDQ_C1") (pintype "power_in"))
      (node (ref "D9") (pin "D1") (pinfunction "VDD_D1") (pintype "passive"))
      (node (ref "D9") (pin "D9") (pinfunction "VDDQ_D9") (pintype "power_in"))
      (node (ref "D9") (pin "F2") (pinfunction "VDDQ_F2") (pintype "power_in"))
      (node (ref "D9") (pin "F8") (pinfunction "VDDQ_F8") (pintype "power_in"))
      (node (ref "D9") (pin "G1") (pinfunction "VDDQ_G1") (pintype "power_in"))
      (node (ref "D9") (pin "G7") (pinfunction "VDD_G7") (pintype "passive"))
      (node (ref "D9") (pin "G9") (pinfunction "VDDQ_G9") (pintype "power_in"))
      (node (ref "D9") (pin "J1") (pinfunction "VDD_J1") (pintype "passive"))
      (node (ref "D9") (pin "J2") (pinfunction "VDDQ_J2") (pintype "power_in"))
      (node (ref "D9") (pin "J8") (pinfunction "VDDQ_J8") (pintype "power_in"))
      (node (ref "D9") (pin "J9") (pinfunction "VDD_J9") (pintype "passive"))
      (node (ref "D9") (pin "L1") (pinfunction "VDD_L1") (pintype "passive"))
      (node (ref "D9") (pin "L9") (pinfunction "VDD_L9") (pintype "passive"))
      (node (ref "D9") (pin "R1") (pinfunction "VDD_R1") (pintype "passive"))
      (node (ref "D9") (pin "T9") (pinfunction "VDD_T9") (pintype "passive"))
      (node (ref "R64") (pin "1") (pinfunction "1_1") (pintype "passive"))
      (node (ref "R65") (pin "1") (pinfunction "1_1") (pintype "passive"))
      (node (ref "R66") (pin "1") (pinfunction "1_1") (pintype "passive"))
      (node (ref "R67") (pin "1") (pinfunction "1_1") (pintype "passive"))
      (node (ref "R68") (pin "1") (pinfunction "1_1") (pintype "passive"))
      (node (ref "R69") (pin "1") (pinfunction "1_1") (pintype "passive"))
      (node (ref "R70") (pin "1") (pinfunction "1_1") (pintype "passive"))
      (node (ref "R71") (pin "1") (pinfunction "1_1") (pintype "passive"))
      (node (ref "R72") (pin "1") (pinfunction "1_1") (pintype "passive"))
      (node (ref "R73") (pin "1") (pinfunction "1_1") (pintype "passive"))
      (node (ref "R74") (pin "1") (pinfunction "1_1") (pintype "passive"))
      (node (ref "R75") (pin "1") (pinfunction "1_1") (pintype "passive"))
      (node (ref "R76") (pin "1") (pinfunction "1_1") (pintype "passive"))
      (node (ref "R77") (pin "1") (pinfunction "1_1") (pintype "passive"))
      (node (ref "R78") (pin "1") (pinfunction "1_1") (pintype "passive"))
      (node (ref "R80") (pin "2") (pinfunction "2_2") (pintype "passive"))
      (node (ref "R81") (pin "2") (pinfunction "2_2") (pintype "passive"))
      (node (ref "R82") (pin "2") (pinfunction "2_2") (pintype "passive"))
    )
    (net (code "88") (name "/Vref_DDR4") (class "Default")
      (node (ref "C337") (pin "2") (pinfunction "2_2") (pintype "passive"))
      (node (ref "C338") (pin "2") (pinfunction "2_2") (pintype "passive"))
      (node (ref "C339") (pin "2") (pinfunction "2_2") (pintype "passive"))
      (node (ref "D10") (pin "M1") (pinfunction "VREFCA_M1") (pintype "passive"))
      (node (ref "D9") (pin "M1") (pinfunction "VREFCA_M1") (pintype "passive"))
      (node (ref "R64") (pin "2") (pinfunction "2_2") (pintype "passive"))
      (node (ref "R79") (pin "2") (pinfunction "2_2") (pintype "passive"))
    )
    (net (code "89") (name "/WEn") (class "Default")
      (node (ref "D10") (pin "L2") (pinfunction "WE_N/A14_L2") (pintype "input"))
      (node (ref "D9") (pin "L2") (pinfunction "WE_N/A14_L2") (pintype "input"))
    )
    (net (code "96") (name "GND") (class "Default")
      (node (ref "C337") (pin "1") (pinfunction "1_1") (pintype "passive"))
      (node (ref "C338") (pin "1") (pinfunction "1_1") (pintype "passive"))
      (node (ref "C339") (pin "1") (pinfunction "1_1") (pintype "passive"))
      (node (ref "C340") (pin "1") (pinfunction "1_1") (pintype "passive"))
      (node (ref "C341") (pin "1") (pinfunction "1_1") (pintype "passive"))
      (node (ref "C342") (pin "1") (pinfunction "1_1") (pintype "passive"))
      (node (ref "C343") (pin "1") (pinfunction "1_1") (pintype "passive"))
      (node (ref "C344") (pin "1") (pinfunction "1_1") (pintype "passive"))
      (node (ref "C345") (pin "1") (pinfunction "1_1") (pintype "passive"))
      (node (ref "C346") (pin "1") (pinfunction "1_1") (pintype "passive"))
      (node (ref "C347") (pin "1") (pinfunction "1_1") (pintype "passive"))
      (node (ref "C348") (pin "1") (pinfunction "1_1") (pintype "passive"))
      (node (ref "C349") (pin "1") (pinfunction "1_1") (pintype "passive"))
      (node (ref "C350") (pin "1") (pinfunction "1_1") (pintype "passive"))
      (node (ref "C351") (pin "1") (pinfunction "1_1") (pintype "passive"))
      (node (ref "C352") (pin "1") (pinfunction "1_1") (pintype "passive"))
      (node (ref "C353") (pin "1") (pinfunction "1_1") (pintype "passive"))
      (node (ref "C354") (pin "1") (pinfunction "1_1") (pintype "passive"))
      (node (ref "C355") (pin "1") (pinfunction "1_1") (pintype "passive"))
      (node (ref "D10") (pin "A2") (pinfunction "VSSQ_A2") (pintype "power_in"))
      (node (ref "D10") (pin "A8") (pinfunction "VSSQ_A8") (pintype "power_in"))
      (node (ref "D10") (pin "B2") (pinfunction "VSS_B2") (pintype "power_in"))
      (node (ref "D10") (pin "C9") (pinfunction "VSSQ_C9") (pintype "power_in"))
      (node (ref "D10") (pin "D2") (pinfunction "VSSQ_D2") (pintype "power_in"))
      (node (ref "D10") (pin "D8") (pinfunction "VSSQ_D8") (pintype "power_in"))
      (node (ref "D10") (pin "E1") (pinfunction "VSS_E1") (pintype "power_in"))
      (node (ref "D10") (pin "E3") (pinfunction "VSSQ_E3") (pintype "power_in"))
      (node (ref "D10") (pin "E8") (pinfunction "VSSQ_E8") (pintype "power_in"))
      (node (ref "D10") (pin "E9") (pinfunction "VSS_E9") (pintype "power_in"))
      (node (ref "D10") (pin "F1") (pinfunction "VSSQ_F1") (pintype "power_in"))
      (node (ref "D10") (pin "G8") (pinfunction "VSS_G8") (pintype "power_in"))
      (node (ref "D10") (pin "H1") (pinfunction "VSSQ_H1") (pintype "power_in"))
      (node (ref "D10") (pin "H9") (pinfunction "VSSQ_H9") (pintype "power_in"))
      (node (ref "D10") (pin "K1") (pinfunction "VSS_K1") (pintype "power_in"))
      (node (ref "D10") (pin "K9") (pinfunction "VSS_K9") (pintype "power_in"))
      (node (ref "D10") (pin "M9") (pinfunction "VSS_M9") (pintype "power_in"))
      (node (ref "D10") (pin "N1") (pinfunction "VSS_N1") (pintype "power_in"))
      (node (ref "D10") (pin "N9") (pinfunction "TEN_N9") (pintype "input"))
      (node (ref "D10") (pin "T1") (pinfunction "VSS_T1") (pintype "power_in"))
      (node (ref "D9") (pin "A2") (pinfunction "VSSQ_A2") (pintype "power_in"))
      (node (ref "D9") (pin "A8") (pinfunction "VSSQ_A8") (pintype "power_in"))
      (node (ref "D9") (pin "B2") (pinfunction "VSS_B2") (pintype "power_in"))
      (node (ref "D9") (pin "C9") (pinfunction "VSSQ_C9") (pintype "power_in"))
      (node (ref "D9") (pin "D2") (pinfunction "VSSQ_D2") (pintype "power_in"))
      (node (ref "D9") (pin "D8") (pinfunction "VSSQ_D8") (pintype "power_in"))
      (node (ref "D9") (pin "E1") (pinfunction "VSS_E1") (pintype "power_in"))
      (node (ref "D9") (pin "E3") (pinfunction "VSSQ_E3") (pintype "power_in"))
      (node (ref "D9") (pin "E8") (pinfunction "VSSQ_E8") (pintype "power_in"))
      (node (ref "D9") (pin "E9") (pinfunction "VSS_E9") (pintype "power_in"))
      (node (ref "D9") (pin "F1") (pinfunction "VSSQ_F1") (pintype "power_in"))
      (node (ref "D9") (pin "G8") (pinfunction "VSS_G8") (pintype "power_in"))
      (node (ref "D9") (pin "H1") (pinfunction "VSSQ_H1") (pintype "power_in"))
      (node (ref "D9") (pin "H9") (pinfunction "VSSQ_H9") (pintype "power_in"))
      (node (ref "D9") (pin "K1") (pinfunction "VSS_K1") (pintype "power_in"))
      (node (ref "D9") (pin "K9") (pinfunction "VSS_K9") (pintype "power_in"))
      (node (ref "D9") (pin "M9") (pinfunction "VSS_M9") (pintype "power_in"))
      (node (ref "D9") (pin "N1") (pinfunction "VSS_N1") (pintype "power_in"))
      (node (ref "D9") (pin "N9") (pinfunction "TEN_N9") (pintype "input"))
      (node (ref "D9") (pin "T1") (pinfunction "VSS_T1") (pintype "power_in"))
      (node (ref "R79") (pin "1") (pinfunction "1_1") (pintype "passive"))
    )
    (net (code "97") (name "Net-(D9B-ZQ)") (class "Default")
      (node (ref "D9") (pin "F9") (pinfunction "ZQ_F9") (pintype "passive"))
      (node (ref "R80") (pin "1") (pinfunction "1_1") (pintype "passive"))
    )
    (net (code "98") (name "Net-(D10B-ZQ)") (class "Default")
      (node (ref "D10") (pin "F9") (pinfunction "ZQ_F9") (pintype "passive"))
      (node (ref "R81") (pin "1") (pinfunction "1_1") (pintype "passive"))
    )
    (net (code "99") (name "unconnected-(D9B-NC-PadT7)") (class "Default")
      (node (ref "D9") (pin "T7") (pinfunction "NC_T7") (pintype "passive"))
    )
    (net (code "100") (name "unconnected-(D10B-NC-PadT7)") (class "Default")
      (node (ref "D10") (pin "T7") (pinfunction "NC_T7") (pintype "passive"))
    )
  )
)
